# testbrd.net
KiCad netlist of a schematic drawn in EAGLE
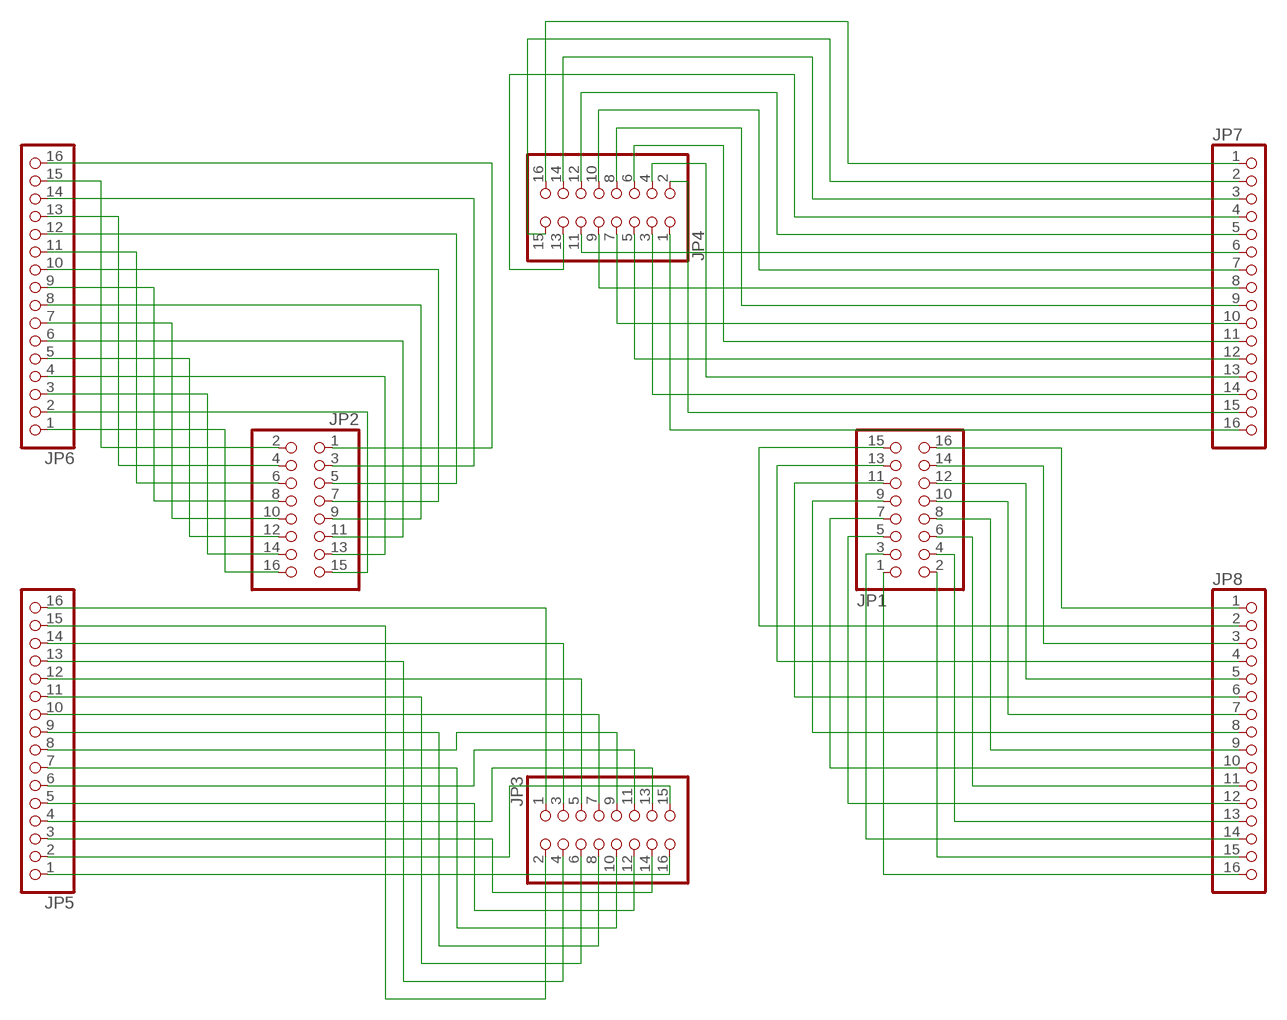
[diagram p0: schematic, sheet 1]

(export (version "E")
  (design (tool "Eeschema 10.0.6"))
  (components
    (comp (ref "JP1")
      (value "PINHD-2X8")
      (footprint "eagle-import:2X08")
      (libsource (lib "eagle-import") (part "PINHD-2X8"))
    )
    (comp (ref "JP2")
      (value "PINHD-2X8")
      (footprint "eagle-import:2X08")
      (libsource (lib "eagle-import") (part "PINHD-2X8"))
    )
    (comp (ref "JP3")
      (value "PINHD-2X8")
      (footprint "eagle-import:2X08")
      (libsource (lib "eagle-import") (part "PINHD-2X8"))
    )
    (comp (ref "JP4")
      (value "PINHD-2X8")
      (footprint "eagle-import:2X08")
      (libsource (lib "eagle-import") (part "PINHD-2X8"))
    )
    (comp (ref "JP5")
      (value "PINHD-1X16")
      (footprint "eagle-import:1X16")
      (libsource (lib "eagle-import") (part "PINHD-1X16"))
    )
    (comp (ref "JP6")
      (value "PINHD-1X16")
      (footprint "eagle-import:1X16")
      (libsource (lib "eagle-import") (part "PINHD-1X16"))
    )
    (comp (ref "JP7")
      (value "PINHD-1X16")
      (footprint "eagle-import:1X16")
      (libsource (lib "eagle-import") (part "PINHD-1X16"))
    )
    (comp (ref "JP8")
      (value "PINHD-1X16")
      (footprint "eagle-import:1X16")
      (libsource (lib "eagle-import") (part "PINHD-1X16"))
    )
  )
  (nets
    (net (code "1") (name "Net-(JP1-Pad1)") (class "Default")
      (node (ref "JP1") (pin "1") (pinfunction "1_1") (pintype "passive"))
      (node (ref "JP8") (pin "16") (pinfunction "16_16") (pintype "passive"))
    )
    (net (code "2") (name "Net-(JP1-Pad2)") (class "Default")
      (node (ref "JP1") (pin "2") (pinfunction "2_2") (pintype "passive"))
      (node (ref "JP8") (pin "15") (pinfunction "15_15") (pintype "passive"))
    )
    (net (code "3") (name "Net-(JP1-Pad3)") (class "Default")
      (node (ref "JP1") (pin "3") (pinfunction "3_3") (pintype "passive"))
      (node (ref "JP8") (pin "14") (pinfunction "14_14") (pintype "passive"))
    )
    (net (code "4") (name "Net-(JP1-Pad4)") (class "Default")
      (node (ref "JP1") (pin "4") (pinfunction "4_4") (pintype "passive"))
      (node (ref "JP8") (pin "13") (pinfunction "13_13") (pintype "passive"))
    )
    (net (code "5") (name "Net-(JP1-Pad5)") (class "Default")
      (node (ref "JP1") (pin "5") (pinfunction "5_5") (pintype "passive"))
      (node (ref "JP8") (pin "12") (pinfunction "12_12") (pintype "passive"))
    )
    (net (code "6") (name "Net-(JP1-Pad6)") (class "Default")
      (node (ref "JP1") (pin "6") (pinfunction "6_6") (pintype "passive"))
      (node (ref "JP8") (pin "11") (pinfunction "11_11") (pintype "passive"))
    )
    (net (code "7") (name "Net-(JP1-Pad7)") (class "Default")
      (node (ref "JP1") (pin "7") (pinfunction "7_7") (pintype "passive"))
      (node (ref "JP8") (pin "10") (pinfunction "10_10") (pintype "passive"))
    )
    (net (code "8") (name "Net-(JP1-Pad8)") (class "Default")
      (node (ref "JP1") (pin "8") (pinfunction "8_8") (pintype "passive"))
      (node (ref "JP8") (pin "9") (pinfunction "9_9") (pintype "passive"))
    )
    (net (code "9") (name "Net-(JP1-Pad9)") (class "Default")
      (node (ref "JP1") (pin "9") (pinfunction "9_9") (pintype "passive"))
      (node (ref "JP8") (pin "8") (pinfunction "8_8") (pintype "passive"))
    )
    (net (code "10") (name "Net-(JP1-Pad10)") (class "Default")
      (node (ref "JP1") (pin "10") (pinfunction "10_10") (pintype "passive"))
      (node (ref "JP8") (pin "7") (pinfunction "7_7") (pintype "passive"))
    )
    (net (code "11") (name "Net-(JP1-Pad11)") (class "Default")
      (node (ref "JP1") (pin "11") (pinfunction "11_11") (pintype "passive"))
      (node (ref "JP8") (pin "6") (pinfunction "6_6") (pintype "passive"))
    )
    (net (code "12") (name "Net-(JP1-Pad12)") (class "Default")
      (node (ref "JP1") (pin "12") (pinfunction "12_12") (pintype "passive"))
      (node (ref "JP8") (pin "5") (pinfunction "5_5") (pintype "passive"))
    )
    (net (code "13") (name "Net-(JP1-Pad13)") (class "Default")
      (node (ref "JP1") (pin "13") (pinfunction "13_13") (pintype "passive"))
      (node (ref "JP8") (pin "4") (pinfunction "4_4") (pintype "passive"))
    )
    (net (code "14") (name "Net-(JP1-Pad14)") (class "Default")
      (node (ref "JP1") (pin "14") (pinfunction "14_14") (pintype "passive"))
      (node (ref "JP8") (pin "3") (pinfunction "3_3") (pintype "passive"))
    )
    (net (code "15") (name "Net-(JP1-Pad15)") (class "Default")
      (node (ref "JP1") (pin "15") (pinfunction "15_15") (pintype "passive"))
      (node (ref "JP8") (pin "2") (pinfunction "2_2") (pintype "passive"))
    )
    (net (code "16") (name "Net-(JP1-Pad16)") (class "Default")
      (node (ref "JP1") (pin "16") (pinfunction "16_16") (pintype "passive"))
      (node (ref "JP8") (pin "1") (pinfunction "1_1") (pintype "passive"))
    )
    (net (code "17") (name "Net-(JP2-Pad1)") (class "Default")
      (node (ref "JP2") (pin "1") (pinfunction "1_1") (pintype "passive"))
      (node (ref "JP6") (pin "16") (pinfunction "16_16") (pintype "passive"))
    )
    (net (code "18") (name "Net-(JP2-Pad2)") (class "Default")
      (node (ref "JP2") (pin "2") (pinfunction "2_2") (pintype "passive"))
      (node (ref "JP6") (pin "15") (pinfunction "15_15") (pintype "passive"))
    )
    (net (code "19") (name "Net-(JP2-Pad3)") (class "Default")
      (node (ref "JP2") (pin "3") (pinfunction "3_3") (pintype "passive"))
      (node (ref "JP6") (pin "14") (pinfunction "14_14") (pintype "passive"))
    )
    (net (code "20") (name "Net-(JP2-Pad4)") (class "Default")
      (node (ref "JP2") (pin "4") (pinfunction "4_4") (pintype "passive"))
      (node (ref "JP6") (pin "13") (pinfunction "13_13") (pintype "passive"))
    )
    (net (code "21") (name "Net-(JP2-Pad5)") (class "Default")
      (node (ref "JP2") (pin "5") (pinfunction "5_5") (pintype "passive"))
      (node (ref "JP6") (pin "12") (pinfunction "12_12") (pintype "passive"))
    )
    (net (code "22") (name "Net-(JP2-Pad6)") (class "Default")
      (node (ref "JP2") (pin "6") (pinfunction "6_6") (pintype "passive"))
      (node (ref "JP6") (pin "11") (pinfunction "11_11") (pintype "passive"))
    )
    (net (code "23") (name "Net-(JP2-Pad7)") (class "Default")
      (node (ref "JP2") (pin "7") (pinfunction "7_7") (pintype "passive"))
      (node (ref "JP6") (pin "10") (pinfunction "10_10") (pintype "passive"))
    )
    (net (code "24") (name "Net-(JP2-Pad8)") (class "Default")
      (node (ref "JP2") (pin "8") (pinfunction "8_8") (pintype "passive"))
      (node (ref "JP6") (pin "9") (pinfunction "9_9") (pintype "passive"))
    )
    (net (code "25") (name "Net-(JP2-Pad9)") (class "Default")
      (node (ref "JP2") (pin "9") (pinfunction "9_9") (pintype "passive"))
      (node (ref "JP6") (pin "8") (pinfunction "8_8") (pintype "passive"))
    )
    (net (code "26") (name "Net-(JP2-Pad10)") (class "Default")
      (node (ref "JP2") (pin "10") (pinfunction "10_10") (pintype "passive"))
      (node (ref "JP6") (pin "7") (pinfunction "7_7") (pintype "passive"))
    )
    (net (code "27") (name "Net-(JP2-Pad11)") (class "Default")
      (node (ref "JP2") (pin "11") (pinfunction "11_11") (pintype "passive"))
      (node (ref "JP6") (pin "6") (pinfunction "6_6") (pintype "passive"))
    )
    (net (code "28") (name "Net-(JP2-Pad12)") (class "Default")
      (node (ref "JP2") (pin "12") (pinfunction "12_12") (pintype "passive"))
      (node (ref "JP6") (pin "5") (pinfunction "5_5") (pintype "passive"))
    )
    (net (code "29") (name "Net-(JP2-Pad13)") (class "Default")
      (node (ref "JP2") (pin "13") (pinfunction "13_13") (pintype "passive"))
      (node (ref "JP6") (pin "4") (pinfunction "4_4") (pintype "passive"))
    )
    (net (code "30") (name "Net-(JP2-Pad14)") (class "Default")
      (node (ref "JP2") (pin "14") (pinfunction "14_14") (pintype "passive"))
      (node (ref "JP6") (pin "3") (pinfunction "3_3") (pintype "passive"))
    )
    (net (code "31") (name "Net-(JP2-Pad15)") (class "Default")
      (node (ref "JP2") (pin "15") (pinfunction "15_15") (pintype "passive"))
      (node (ref "JP6") (pin "2") (pinfunction "2_2") (pintype "passive"))
    )
    (net (code "32") (name "Net-(JP2-Pad16)") (class "Default")
      (node (ref "JP2") (pin "16") (pinfunction "16_16") (pintype "passive"))
      (node (ref "JP6") (pin "1") (pinfunction "1_1") (pintype "passive"))
    )
    (net (code "33") (name "Net-(JP3-Pad1)") (class "Default")
      (node (ref "JP3") (pin "1") (pinfunction "1_1") (pintype "passive"))
      (node (ref "JP5") (pin "16") (pinfunction "16_16") (pintype "passive"))
    )
    (net (code "34") (name "Net-(JP3-Pad2)") (class "Default")
      (node (ref "JP3") (pin "2") (pinfunction "2_2") (pintype "passive"))
      (node (ref "JP5") (pin "15") (pinfunction "15_15") (pintype "passive"))
    )
    (net (code "35") (name "Net-(JP3-Pad3)") (class "Default")
      (node (ref "JP3") (pin "3") (pinfunction "3_3") (pintype "passive"))
      (node (ref "JP5") (pin "14") (pinfunction "14_14") (pintype "passive"))
    )
    (net (code "36") (name "Net-(JP3-Pad4)") (class "Default")
      (node (ref "JP3") (pin "4") (pinfunction "4_4") (pintype "passive"))
      (node (ref "JP5") (pin "13") (pinfunction "13_13") (pintype "passive"))
    )
    (net (code "37") (name "Net-(JP3-Pad5)") (class "Default")
      (node (ref "JP3") (pin "5") (pinfunction "5_5") (pintype "passive"))
      (node (ref "JP5") (pin "12") (pinfunction "12_12") (pintype "passive"))
    )
    (net (code "38") (name "Net-(JP3-Pad6)") (class "Default")
      (node (ref "JP3") (pin "6") (pinfunction "6_6") (pintype "passive"))
      (node (ref "JP5") (pin "11") (pinfunction "11_11") (pintype "passive"))
    )
    (net (code "39") (name "Net-(JP3-Pad7)") (class "Default")
      (node (ref "JP3") (pin "7") (pinfunction "7_7") (pintype "passive"))
      (node (ref "JP5") (pin "10") (pinfunction "10_10") (pintype "passive"))
    )
    (net (code "40") (name "Net-(JP3-Pad8)") (class "Default")
      (node (ref "JP3") (pin "8") (pinfunction "8_8") (pintype "passive"))
      (node (ref "JP5") (pin "9") (pinfunction "9_9") (pintype "passive"))
    )
    (net (code "41") (name "Net-(JP3-Pad9)") (class "Default")
      (node (ref "JP3") (pin "9") (pinfunction "9_9") (pintype "passive"))
      (node (ref "JP5") (pin "8") (pinfunction "8_8") (pintype "passive"))
    )
    (net (code "42") (name "Net-(JP3-Pad10)") (class "Default")
      (node (ref "JP3") (pin "10") (pinfunction "10_10") (pintype "passive"))
      (node (ref "JP5") (pin "7") (pinfunction "7_7") (pintype "passive"))
    )
    (net (code "43") (name "Net-(JP3-Pad11)") (class "Default")
      (node (ref "JP3") (pin "11") (pinfunction "11_11") (pintype "passive"))
      (node (ref "JP5") (pin "6") (pinfunction "6_6") (pintype "passive"))
    )
    (net (code "44") (name "Net-(JP3-Pad12)") (class "Default")
      (node (ref "JP3") (pin "12") (pinfunction "12_12") (pintype "passive"))
      (node (ref "JP5") (pin "5") (pinfunction "5_5") (pintype "passive"))
    )
    (net (code "45") (name "Net-(JP3-Pad13)") (class "Default")
      (node (ref "JP3") (pin "13") (pinfunction "13_13") (pintype "passive"))
      (node (ref "JP5") (pin "4") (pinfunction "4_4") (pintype "passive"))
    )
    (net (code "46") (name "Net-(JP3-Pad14)") (class "Default")
      (node (ref "JP3") (pin "14") (pinfunction "14_14") (pintype "passive"))
      (node (ref "JP5") (pin "3") (pinfunction "3_3") (pintype "passive"))
    )
    (net (code "47") (name "Net-(JP3-Pad15)") (class "Default")
      (node (ref "JP3") (pin "15") (pinfunction "15_15") (pintype "passive"))
      (node (ref "JP5") (pin "2") (pinfunction "2_2") (pintype "passive"))
    )
    (net (code "48") (name "Net-(JP3-Pad16)") (class "Default")
      (node (ref "JP3") (pin "16") (pinfunction "16_16") (pintype "passive"))
      (node (ref "JP5") (pin "1") (pinfunction "1_1") (pintype "passive"))
    )
    (net (code "49") (name "Net-(JP4-Pad1)") (class "Default")
      (node (ref "JP4") (pin "1") (pinfunction "1_1") (pintype "passive"))
      (node (ref "JP7") (pin "16") (pinfunction "16_16") (pintype "passive"))
    )
    (net (code "50") (name "Net-(JP4-Pad2)") (class "Default")
      (node (ref "JP4") (pin "2") (pinfunction "2_2") (pintype "passive"))
      (node (ref "JP7") (pin "15") (pinfunction "15_15") (pintype "passive"))
    )
    (net (code "51") (name "Net-(JP4-Pad3)") (class "Default")
      (node (ref "JP4") (pin "3") (pinfunction "3_3") (pintype "passive"))
      (node (ref "JP7") (pin "14") (pinfunction "14_14") (pintype "passive"))
    )
    (net (code "52") (name "Net-(JP4-Pad4)") (class "Default")
      (node (ref "JP4") (pin "4") (pinfunction "4_4") (pintype "passive"))
      (node (ref "JP7") (pin "13") (pinfunction "13_13") (pintype "passive"))
    )
    (net (code "53") (name "Net-(JP4-Pad5)") (class "Default")
      (node (ref "JP4") (pin "5") (pinfunction "5_5") (pintype "passive"))
      (node (ref "JP7") (pin "12") (pinfunction "12_12") (pintype "passive"))
    )
    (net (code "54") (name "Net-(JP4-Pad6)") (class "Default")
      (node (ref "JP4") (pin "6") (pinfunction "6_6") (pintype "passive"))
      (node (ref "JP7") (pin "11") (pinfunction "11_11") (pintype "passive"))
    )
    (net (code "55") (name "Net-(JP4-Pad7)") (class "Default")
      (node (ref "JP4") (pin "7") (pinfunction "7_7") (pintype "passive"))
      (node (ref "JP7") (pin "10") (pinfunction "10_10") (pintype "passive"))
    )
    (net (code "56") (name "Net-(JP4-Pad8)") (class "Default")
      (node (ref "JP4") (pin "8") (pinfunction "8_8") (pintype "passive"))
      (node (ref "JP7") (pin "9") (pinfunction "9_9") (pintype "passive"))
    )
    (net (code "57") (name "Net-(JP4-Pad9)") (class "Default")
      (node (ref "JP4") (pin "9") (pinfunction "9_9") (pintype "passive"))
      (node (ref "JP7") (pin "8") (pinfunction "8_8") (pintype "passive"))
    )
    (net (code "58") (name "Net-(JP4-Pad10)") (class "Default")
      (node (ref "JP4") (pin "10") (pinfunction "10_10") (pintype "passive"))
      (node (ref "JP7") (pin "7") (pinfunction "7_7") (pintype "passive"))
    )
    (net (code "59") (name "Net-(JP4-Pad11)") (class "Default")
      (node (ref "JP4") (pin "11") (pinfunction "11_11") (pintype "passive"))
      (node (ref "JP7") (pin "6") (pinfunction "6_6") (pintype "passive"))
    )
    (net (code "60") (name "Net-(JP4-Pad12)") (class "Default")
      (node (ref "JP4") (pin "12") (pinfunction "12_12") (pintype "passive"))
      (node (ref "JP7") (pin "5") (pinfunction "5_5") (pintype "passive"))
    )
    (net (code "61") (name "Net-(JP4-Pad13)") (class "Default")
      (node (ref "JP4") (pin "13") (pinfunction "13_13") (pintype "passive"))
      (node (ref "JP7") (pin "4") (pinfunction "4_4") (pintype "passive"))
    )
    (net (code "62") (name "Net-(JP4-Pad14)") (class "Default")
      (node (ref "JP4") (pin "14") (pinfunction "14_14") (pintype "passive"))
      (node (ref "JP7") (pin "3") (pinfunction "3_3") (pintype "passive"))
    )
    (net (code "63") (name "Net-(JP4-Pad15)") (class "Default")
      (node (ref "JP4") (pin "15") (pinfunction "15_15") (pintype "passive"))
      (node (ref "JP7") (pin "2") (pinfunction "2_2") (pintype "passive"))
    )
    (net (code "64") (name "Net-(JP4-Pad16)") (class "Default")
      (node (ref "JP4") (pin "16") (pinfunction "16_16") (pintype "passive"))
      (node (ref "JP7") (pin "1") (pinfunction "1_1") (pintype "passive"))
    )
  )
)
